# Sheet1.net
KiCad netlist of a schematic drawn in Altium Designer
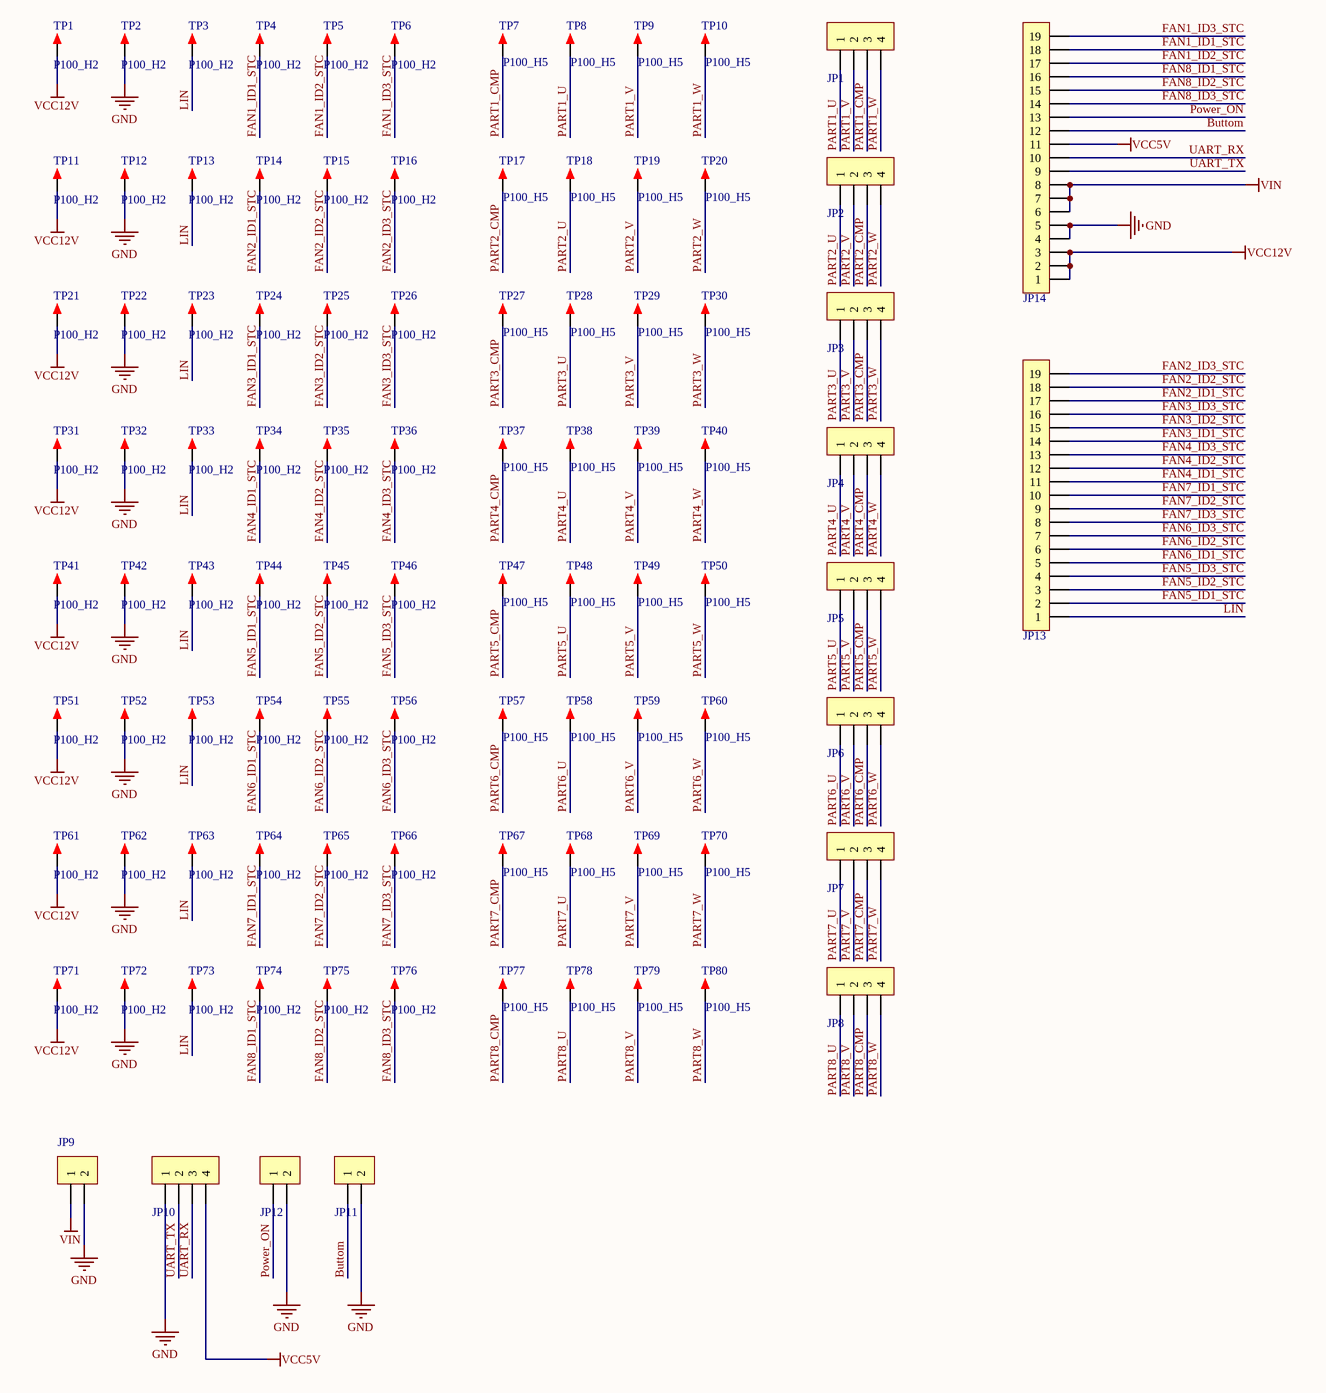
[diagram p0: Sheet1.SchDoc]

(export (version "E")
  (design (tool "Eeschema 10.0.6"))
  (components
    (comp (ref "JP1")
      (value "HDR-1X4")
      (footprint "XH2.54-WS-4P")
      (description "4P接插件")
      (fields (field (name "版权归属") "源创客"))
      (libsource (lib "Connector-PinHeader") (part "Header 4"))
    )
    (comp (ref "JP2")
      (value "HDR-1X4")
      (footprint "XH2.54-WS-4P")
      (description "4P接插件")
      (fields (field (name "版权归属") "源创客"))
      (libsource (lib "Connector-PinHeader") (part "Header 4"))
    )
    (comp (ref "JP3")
      (value "HDR-1X4")
      (footprint "XH2.54-WS-4P")
      (description "4P接插件")
      (fields (field (name "版权归属") "源创客"))
      (libsource (lib "Connector-PinHeader") (part "Header 4"))
    )
    (comp (ref "JP4")
      (value "HDR-1X4")
      (footprint "XH2.54-WS-4P")
      (description "4P接插件")
      (fields (field (name "版权归属") "源创客"))
      (libsource (lib "Connector-PinHeader") (part "Header 4"))
    )
    (comp (ref "JP5")
      (value "HDR-1X4")
      (footprint "XH2.54-WS-4P")
      (description "4P接插件")
      (fields (field (name "版权归属") "源创客"))
      (libsource (lib "Connector-PinHeader") (part "Header 4"))
    )
    (comp (ref "JP6")
      (value "HDR-1X4")
      (footprint "XH2.54-WS-4P")
      (description "4P接插件")
      (fields (field (name "版权归属") "源创客"))
      (libsource (lib "Connector-PinHeader") (part "Header 4"))
    )
    (comp (ref "JP7")
      (value "HDR-1X4")
      (footprint "XH2.54-WS-4P")
      (description "4P接插件")
      (fields (field (name "版权归属") "源创客"))
      (libsource (lib "Connector-PinHeader") (part "Header 4"))
    )
    (comp (ref "JP8")
      (value "HDR-1X4")
      (footprint "XH2.54-WS-4P")
      (description "4P接插件")
      (fields (field (name "版权归属") "源创客"))
      (libsource (lib "Connector-PinHeader") (part "Header 4"))
    )
    (comp (ref "JP9")
      (value "HDR-1X2")
      (footprint "DC-005P")
      (description "2P接插件")
      (fields (field (name "版权归属") "源创客"))
      (libsource (lib "Connector-PinHeader") (part "Header 2"))
    )
    (comp (ref "JP10")
      (value "HDR-1X4")
      (footprint "XH2.54-WS-4P")
      (description "4P接插件")
      (fields (field (name "版权归属") "源创客"))
      (libsource (lib "Connector-PinHeader") (part "Header 4"))
    )
    (comp (ref "JP11")
      (value "HDR-1X2")
      (footprint "XH2.54-WS-2P")
      (description "2P接插件")
      (fields (field (name "版权归属") "源创客"))
      (libsource (lib "Connector-PinHeader") (part "Header 2"))
    )
    (comp (ref "JP12")
      (value "HDR-1X2")
      (footprint "XH2.54-WS-2P")
      (description "2P接插件")
      (fields (field (name "版权归属") "源创客"))
      (libsource (lib "Connector-PinHeader") (part "Header 2"))
    )
    (comp (ref "JP13")
      (value "HDR-1X19")
      (footprint "贴片排针2.54mm_交错_19P")
      (description "19P接插件")
      (fields (field (name "版权归属") "源创客"))
      (libsource (lib "Connector-PinHeader") (part "Header 19"))
    )
    (comp (ref "JP14")
      (value "HDR-1X19")
      (footprint "贴片排针2.54mm_交错_19P")
      (description "19P接插件")
      (fields (field (name "版权归属") "源创客"))
      (libsource (lib "Connector-PinHeader") (part "Header 19"))
    )
    (comp (ref "TP1")
      (value "P100_H2")
      (footprint "P100_H2")
      (description "测试点")
      (fields (field (name "版权归属") "源创客"))
      (libsource (lib "Hole") (part "TEST"))
    )
    (comp (ref "TP2")
      (value "P100_H2")
      (footprint "P100_H2")
      (description "测试点")
      (fields (field (name "版权归属") "源创客"))
      (libsource (lib "Hole") (part "TEST"))
    )
    (comp (ref "TP3")
      (value "P100_H2")
      (footprint "P100_H2")
      (description "测试点")
      (fields (field (name "版权归属") "源创客"))
      (libsource (lib "Hole") (part "TEST"))
    )
    (comp (ref "TP4")
      (value "P100_H2")
      (footprint "P100_H2")
      (description "测试点")
      (fields (field (name "版权归属") "源创客"))
      (libsource (lib "Hole") (part "TEST"))
    )
    (comp (ref "TP5")
      (value "P100_H2")
      (footprint "P100_H2")
      (description "测试点")
      (fields (field (name "版权归属") "源创客"))
      (libsource (lib "Hole") (part "TEST"))
    )
    (comp (ref "TP6")
      (value "P100_H2")
      (footprint "P100_H2")
      (description "测试点")
      (fields (field (name "版权归属") "源创客"))
      (libsource (lib "Hole") (part "TEST"))
    )
    (comp (ref "TP7")
      (value "P100_H5")
      (footprint "P100_H5")
      (description "测试点")
      (fields (field (name "版权归属") "源创客"))
      (libsource (lib "Hole") (part "TEST"))
    )
    (comp (ref "TP8")
      (value "P100_H5")
      (footprint "P100_H5")
      (description "测试点")
      (fields (field (name "版权归属") "源创客"))
      (libsource (lib "Hole") (part "TEST"))
    )
    (comp (ref "TP9")
      (value "P100_H5")
      (footprint "P100_H5")
      (description "测试点")
      (fields (field (name "版权归属") "源创客"))
      (libsource (lib "Hole") (part "TEST"))
    )
    (comp (ref "TP10")
      (value "P100_H5")
      (footprint "P100_H5")
      (description "测试点")
      (fields (field (name "版权归属") "源创客"))
      (libsource (lib "Hole") (part "TEST"))
    )
    (comp (ref "TP11")
      (value "P100_H2")
      (footprint "P100_H2")
      (description "测试点")
      (fields (field (name "版权归属") "源创客"))
      (libsource (lib "Hole") (part "TEST"))
    )
    (comp (ref "TP12")
      (value "P100_H2")
      (footprint "P100_H2")
      (description "测试点")
      (fields (field (name "版权归属") "源创客"))
      (libsource (lib "Hole") (part "TEST"))
    )
    (comp (ref "TP13")
      (value "P100_H2")
      (footprint "P100_H2")
      (description "测试点")
      (fields (field (name "版权归属") "源创客"))
      (libsource (lib "Hole") (part "TEST"))
    )
    (comp (ref "TP14")
      (value "P100_H2")
      (footprint "P100_H2")
      (description "测试点")
      (fields (field (name "版权归属") "源创客"))
      (libsource (lib "Hole") (part "TEST"))
    )
    (comp (ref "TP15")
      (value "P100_H2")
      (footprint "P100_H2")
      (description "测试点")
      (fields (field (name "版权归属") "源创客"))
      (libsource (lib "Hole") (part "TEST"))
    )
    (comp (ref "TP16")
      (value "P100_H2")
      (footprint "P100_H2")
      (description "测试点")
      (fields (field (name "版权归属") "源创客"))
      (libsource (lib "Hole") (part "TEST"))
    )
    (comp (ref "TP17")
      (value "P100_H5")
      (footprint "P100_H5")
      (description "测试点")
      (fields (field (name "版权归属") "源创客"))
      (libsource (lib "Hole") (part "TEST"))
    )
    (comp (ref "TP18")
      (value "P100_H5")
      (footprint "P100_H5")
      (description "测试点")
      (fields (field (name "版权归属") "源创客"))
      (libsource (lib "Hole") (part "TEST"))
    )
    (comp (ref "TP19")
      (value "P100_H5")
      (footprint "P100_H5")
      (description "测试点")
      (fields (field (name "版权归属") "源创客"))
      (libsource (lib "Hole") (part "TEST"))
    )
    (comp (ref "TP20")
      (value "P100_H5")
      (footprint "P100_H5")
      (description "测试点")
      (fields (field (name "版权归属") "源创客"))
      (libsource (lib "Hole") (part "TEST"))
    )
    (comp (ref "TP21")
      (value "P100_H2")
      (footprint "P100_H2")
      (description "测试点")
      (fields (field (name "版权归属") "源创客"))
      (libsource (lib "Hole") (part "TEST"))
    )
    (comp (ref "TP22")
      (value "P100_H2")
      (footprint "P100_H2")
      (description "测试点")
      (fields (field (name "版权归属") "源创客"))
      (libsource (lib "Hole") (part "TEST"))
    )
    (comp (ref "TP23")
      (value "P100_H2")
      (footprint "P100_H2")
      (description "测试点")
      (fields (field (name "版权归属") "源创客"))
      (libsource (lib "Hole") (part "TEST"))
    )
    (comp (ref "TP24")
      (value "P100_H2")
      (footprint "P100_H2")
      (description "测试点")
      (fields (field (name "版权归属") "源创客"))
      (libsource (lib "Hole") (part "TEST"))
    )
    (comp (ref "TP25")
      (value "P100_H2")
      (footprint "P100_H2")
      (description "测试点")
      (fields (field (name "版权归属") "源创客"))
      (libsource (lib "Hole") (part "TEST"))
    )
    (comp (ref "TP26")
      (value "P100_H2")
      (footprint "P100_H2")
      (description "测试点")
      (fields (field (name "版权归属") "源创客"))
      (libsource (lib "Hole") (part "TEST"))
    )
    (comp (ref "TP27")
      (value "P100_H5")
      (footprint "P100_H5")
      (description "测试点")
      (fields (field (name "版权归属") "源创客"))
      (libsource (lib "Hole") (part "TEST"))
    )
    (comp (ref "TP28")
      (value "P100_H5")
      (footprint "P100_H5")
      (description "测试点")
      (fields (field (name "版权归属") "源创客"))
      (libsource (lib "Hole") (part "TEST"))
    )
    (comp (ref "TP29")
      (value "P100_H5")
      (footprint "P100_H5")
      (description "测试点")
      (fields (field (name "版权归属") "源创客"))
      (libsource (lib "Hole") (part "TEST"))
    )
    (comp (ref "TP30")
      (value "P100_H5")
      (footprint "P100_H5")
      (description "测试点")
      (fields (field (name "版权归属") "源创客"))
      (libsource (lib "Hole") (part "TEST"))
    )
    (comp (ref "TP31")
      (value "P100_H2")
      (footprint "P100_H2")
      (description "测试点")
      (fields (field (name "版权归属") "源创客"))
      (libsource (lib "Hole") (part "TEST"))
    )
    (comp (ref "TP32")
      (value "P100_H2")
      (footprint "P100_H2")
      (description "测试点")
      (fields (field (name "版权归属") "源创客"))
      (libsource (lib "Hole") (part "TEST"))
    )
    (comp (ref "TP33")
      (value "P100_H2")
      (footprint "P100_H2")
      (description "测试点")
      (fields (field (name "版权归属") "源创客"))
      (libsource (lib "Hole") (part "TEST"))
    )
    (comp (ref "TP34")
      (value "P100_H2")
      (footprint "P100_H2")
      (description "测试点")
      (fields (field (name "版权归属") "源创客"))
      (libsource (lib "Hole") (part "TEST"))
    )
    (comp (ref "TP35")
      (value "P100_H2")
      (footprint "P100_H2")
      (description "测试点")
      (fields (field (name "版权归属") "源创客"))
      (libsource (lib "Hole") (part "TEST"))
    )
    (comp (ref "TP36")
      (value "P100_H2")
      (footprint "P100_H2")
      (description "测试点")
      (fields (field (name "版权归属") "源创客"))
      (libsource (lib "Hole") (part "TEST"))
    )
    (comp (ref "TP37")
      (value "P100_H5")
      (footprint "P100_H5")
      (description "测试点")
      (fields (field (name "版权归属") "源创客"))
      (libsource (lib "Hole") (part "TEST"))
    )
    (comp (ref "TP38")
      (value "P100_H5")
      (footprint "P100_H5")
      (description "测试点")
      (fields (field (name "版权归属") "源创客"))
      (libsource (lib "Hole") (part "TEST"))
    )
    (comp (ref "TP39")
      (value "P100_H5")
      (footprint "P100_H5")
      (description "测试点")
      (fields (field (name "版权归属") "源创客"))
      (libsource (lib "Hole") (part "TEST"))
    )
    (comp (ref "TP40")
      (value "P100_H5")
      (footprint "P100_H5")
      (description "测试点")
      (fields (field (name "版权归属") "源创客"))
      (libsource (lib "Hole") (part "TEST"))
    )
    (comp (ref "TP41")
      (value "P100_H2")
      (footprint "P100_H2")
      (description "测试点")
      (fields (field (name "版权归属") "源创客"))
      (libsource (lib "Hole") (part "TEST"))
    )
    (comp (ref "TP42")
      (value "P100_H2")
      (footprint "P100_H2")
      (description "测试点")
      (fields (field (name "版权归属") "源创客"))
      (libsource (lib "Hole") (part "TEST"))
    )
    (comp (ref "TP43")
      (value "P100_H2")
      (footprint "P100_H2")
      (description "测试点")
      (fields (field (name "版权归属") "源创客"))
      (libsource (lib "Hole") (part "TEST"))
    )
    (comp (ref "TP44")
      (value "P100_H2")
      (footprint "P100_H2")
      (description "测试点")
      (fields (field (name "版权归属") "源创客"))
      (libsource (lib "Hole") (part "TEST"))
    )
    (comp (ref "TP45")
      (value "P100_H2")
      (footprint "P100_H2")
      (description "测试点")
      (fields (field (name "版权归属") "源创客"))
      (libsource (lib "Hole") (part "TEST"))
    )
    (comp (ref "TP46")
      (value "P100_H2")
      (footprint "P100_H2")
      (description "测试点")
      (fields (field (name "版权归属") "源创客"))
      (libsource (lib "Hole") (part "TEST"))
    )
    (comp (ref "TP47")
      (value "P100_H5")
      (footprint "P100_H5")
      (description "测试点")
      (fields (field (name "版权归属") "源创客"))
      (libsource (lib "Hole") (part "TEST"))
    )
    (comp (ref "TP48")
      (value "P100_H5")
      (footprint "P100_H5")
      (description "测试点")
      (fields (field (name "版权归属") "源创客"))
      (libsource (lib "Hole") (part "TEST"))
    )
    (comp (ref "TP49")
      (value "P100_H5")
      (footprint "P100_H5")
      (description "测试点")
      (fields (field (name "版权归属") "源创客"))
      (libsource (lib "Hole") (part "TEST"))
    )
    (comp (ref "TP50")
      (value "P100_H5")
      (footprint "P100_H5")
      (description "测试点")
      (fields (field (name "版权归属") "源创客"))
      (libsource (lib "Hole") (part "TEST"))
    )
    (comp (ref "TP51")
      (value "P100_H2")
      (footprint "P100_H2")
      (description "测试点")
      (fields (field (name "版权归属") "源创客"))
      (libsource (lib "Hole") (part "TEST"))
    )
    (comp (ref "TP52")
      (value "P100_H2")
      (footprint "P100_H2")
      (description "测试点")
      (fields (field (name "版权归属") "源创客"))
      (libsource (lib "Hole") (part "TEST"))
    )
    (comp (ref "TP53")
      (value "P100_H2")
      (footprint "P100_H2")
      (description "测试点")
      (fields (field (name "版权归属") "源创客"))
      (libsource (lib "Hole") (part "TEST"))
    )
    (comp (ref "TP54")
      (value "P100_H2")
      (footprint "P100_H2")
      (description "测试点")
      (fields (field (name "版权归属") "源创客"))
      (libsource (lib "Hole") (part "TEST"))
    )
    (comp (ref "TP55")
      (value "P100_H2")
      (footprint "P100_H2")
      (description "测试点")
      (fields (field (name "版权归属") "源创客"))
      (libsource (lib "Hole") (part "TEST"))
    )
    (comp (ref "TP56")
      (value "P100_H2")
      (footprint "P100_H2")
      (description "测试点")
      (fields (field (name "版权归属") "源创客"))
      (libsource (lib "Hole") (part "TEST"))
    )
    (comp (ref "TP57")
      (value "P100_H5")
      (footprint "P100_H5")
      (description "测试点")
      (fields (field (name "版权归属") "源创客"))
      (libsource (lib "Hole") (part "TEST"))
    )
    (comp (ref "TP58")
      (value "P100_H5")
      (footprint "P100_H5")
      (description "测试点")
      (fields (field (name "版权归属") "源创客"))
      (libsource (lib "Hole") (part "TEST"))
    )
    (comp (ref "TP59")
      (value "P100_H5")
      (footprint "P100_H5")
      (description "测试点")
      (fields (field (name "版权归属") "源创客"))
      (libsource (lib "Hole") (part "TEST"))
    )
    (comp (ref "TP60")
      (value "P100_H5")
      (footprint "P100_H5")
      (description "测试点")
      (fields (field (name "版权归属") "源创客"))
      (libsource (lib "Hole") (part "TEST"))
    )
    (comp (ref "TP61")
      (value "P100_H2")
      (footprint "P100_H2")
      (description "测试点")
      (fields (field (name "版权归属") "源创客"))
      (libsource (lib "Hole") (part "TEST"))
    )
    (comp (ref "TP62")
      (value "P100_H2")
      (footprint "P100_H2")
      (description "测试点")
      (fields (field (name "版权归属") "源创客"))
      (libsource (lib "Hole") (part "TEST"))
    )
    (comp (ref "TP63")
      (value "P100_H2")
      (footprint "P100_H2")
      (description "测试点")
      (fields (field (name "版权归属") "源创客"))
      (libsource (lib "Hole") (part "TEST"))
    )
    (comp (ref "TP64")
      (value "P100_H2")
      (footprint "P100_H2")
      (description "测试点")
      (fields (field (name "版权归属") "源创客"))
      (libsource (lib "Hole") (part "TEST"))
    )
    (comp (ref "TP65")
      (value "P100_H2")
      (footprint "P100_H2")
      (description "测试点")
      (fields (field (name "版权归属") "源创客"))
      (libsource (lib "Hole") (part "TEST"))
    )
    (comp (ref "TP66")
      (value "P100_H2")
      (footprint "P100_H2")
      (description "测试点")
      (fields (field (name "版权归属") "源创客"))
      (libsource (lib "Hole") (part "TEST"))
    )
    (comp (ref "TP67")
      (value "P100_H5")
      (footprint "P100_H5")
      (description "测试点")
      (fields (field (name "版权归属") "源创客"))
      (libsource (lib "Hole") (part "TEST"))
    )
    (comp (ref "TP68")
      (value "P100_H5")
      (footprint "P100_H5")
      (description "测试点")
      (fields (field (name "版权归属") "源创客"))
      (libsource (lib "Hole") (part "TEST"))
    )
    (comp (ref "TP69")
      (value "P100_H5")
      (footprint "P100_H5")
      (description "测试点")
      (fields (field (name "版权归属") "源创客"))
      (libsource (lib "Hole") (part "TEST"))
    )
    (comp (ref "TP70")
      (value "P100_H5")
      (footprint "P100_H5")
      (description "测试点")
      (fields (field (name "版权归属") "源创客"))
      (libsource (lib "Hole") (part "TEST"))
    )
    (comp (ref "TP71")
      (value "P100_H2")
      (footprint "P100_H2")
      (description "测试点")
      (fields (field (name "版权归属") "源创客"))
      (libsource (lib "Hole") (part "TEST"))
    )
    (comp (ref "TP72")
      (value "P100_H2")
      (footprint "P100_H2")
      (description "测试点")
      (fields (field (name "版权归属") "源创客"))
      (libsource (lib "Hole") (part "TEST"))
    )
    (comp (ref "TP73")
      (value "P100_H2")
      (footprint "P100_H2")
      (description "测试点")
      (fields (field (name "版权归属") "源创客"))
      (libsource (lib "Hole") (part "TEST"))
    )
    (comp (ref "TP74")
      (value "P100_H2")
      (footprint "P100_H2")
      (description "测试点")
      (fields (field (name "版权归属") "源创客"))
      (libsource (lib "Hole") (part "TEST"))
    )
    (comp (ref "TP75")
      (value "P100_H2")
      (footprint "P100_H2")
      (description "测试点")
      (fields (field (name "版权归属") "源创客"))
      (libsource (lib "Hole") (part "TEST"))
    )
    (comp (ref "TP76")
      (value "P100_H2")
      (footprint "P100_H2")
      (description "测试点")
      (fields (field (name "版权归属") "源创客"))
      (libsource (lib "Hole") (part "TEST"))
    )
    (comp (ref "TP77")
      (value "P100_H5")
      (footprint "P100_H5")
      (description "测试点")
      (fields (field (name "版权归属") "源创客"))
      (libsource (lib "Hole") (part "TEST"))
    )
    (comp (ref "TP78")
      (value "P100_H5")
      (footprint "P100_H5")
      (description "测试点")
      (fields (field (name "版权归属") "源创客"))
      (libsource (lib "Hole") (part "TEST"))
    )
    (comp (ref "TP79")
      (value "P100_H5")
      (footprint "P100_H5")
      (description "测试点")
      (fields (field (name "版权归属") "源创客"))
      (libsource (lib "Hole") (part "TEST"))
    )
    (comp (ref "TP80")
      (value "P100_H5")
      (footprint "P100_H5")
      (description "测试点")
      (fields (field (name "版权归属") "源创客"))
      (libsource (lib "Hole") (part "TEST"))
    )
  )
  (nets
    (net (code "1") (name "/Buttom") (class "Default")
      (node (ref "JP11") (pin "1") (pinfunction "1_1") (pintype "passive"))
      (node (ref "JP14") (pin "12") (pinfunction "12_12") (pintype "passive"))
    )
    (net (code "2") (name "/FAN1_ID1_STC") (class "Default")
      (node (ref "JP14") (pin "18") (pinfunction "18_18") (pintype "passive"))
      (node (ref "TP4") (pin "1") (pinfunction "1_1") (pintype "passive"))
    )
    (net (code "3") (name "/FAN1_ID2_STC") (class "Default")
      (node (ref "JP14") (pin "17") (pinfunction "17_17") (pintype "passive"))
      (node (ref "TP5") (pin "1") (pinfunction "1_1") (pintype "passive"))
    )
    (net (code "4") (name "/FAN1_ID3_STC") (class "Default")
      (node (ref "JP14") (pin "19") (pinfunction "19_19") (pintype "passive"))
      (node (ref "TP6") (pin "1") (pinfunction "1_1") (pintype "passive"))
    )
    (net (code "5") (name "/FAN2_ID1_STC") (class "Default")
      (node (ref "JP13") (pin "17") (pinfunction "17_17") (pintype "passive"))
      (node (ref "TP14") (pin "1") (pinfunction "1_1") (pintype "passive"))
    )
    (net (code "6") (name "/FAN2_ID2_STC") (class "Default")
      (node (ref "JP13") (pin "18") (pinfunction "18_18") (pintype "passive"))
      (node (ref "TP15") (pin "1") (pinfunction "1_1") (pintype "passive"))
    )
    (net (code "7") (name "/FAN2_ID3_STC") (class "Default")
      (node (ref "JP13") (pin "19") (pinfunction "19_19") (pintype "passive"))
      (node (ref "TP16") (pin "1") (pinfunction "1_1") (pintype "passive"))
    )
    (net (code "8") (name "/FAN3_ID1_STC") (class "Default")
      (node (ref "JP13") (pin "14") (pinfunction "14_14") (pintype "passive"))
      (node (ref "TP24") (pin "1") (pinfunction "1_1") (pintype "passive"))
    )
    (net (code "9") (name "/FAN3_ID2_STC") (class "Default")
      (node (ref "JP13") (pin "15") (pinfunction "15_15") (pintype "passive"))
      (node (ref "TP25") (pin "1") (pinfunction "1_1") (pintype "passive"))
    )
    (net (code "10") (name "/FAN3_ID3_STC") (class "Default")
      (node (ref "JP13") (pin "16") (pinfunction "16_16") (pintype "passive"))
      (node (ref "TP26") (pin "1") (pinfunction "1_1") (pintype "passive"))
    )
    (net (code "11") (name "/FAN4_ID1_STC") (class "Default")
      (node (ref "JP13") (pin "11") (pinfunction "11_11") (pintype "passive"))
      (node (ref "TP34") (pin "1") (pinfunction "1_1") (pintype "passive"))
    )
    (net (code "12") (name "/FAN4_ID2_STC") (class "Default")
      (node (ref "JP13") (pin "12") (pinfunction "12_12") (pintype "passive"))
      (node (ref "TP35") (pin "1") (pinfunction "1_1") (pintype "passive"))
    )
    (net (code "13") (name "/FAN4_ID3_STC") (class "Default")
      (node (ref "JP13") (pin "13") (pinfunction "13_13") (pintype "passive"))
      (node (ref "TP36") (pin "1") (pinfunction "1_1") (pintype "passive"))
    )
    (net (code "14") (name "/FAN5_ID1_STC") (class "Default")
      (node (ref "JP13") (pin "2") (pinfunction "2_2") (pintype "passive"))
      (node (ref "TP44") (pin "1") (pinfunction "1_1") (pintype "passive"))
    )
    (net (code "15") (name "/FAN5_ID2_STC") (class "Default")
      (node (ref "JP13") (pin "3") (pinfunction "3_3") (pintype "passive"))
      (node (ref "TP45") (pin "1") (pinfunction "1_1") (pintype "passive"))
    )
    (net (code "16") (name "/FAN5_ID3_STC") (class "Default")
      (node (ref "JP13") (pin "4") (pinfunction "4_4") (pintype "passive"))
      (node (ref "TP46") (pin "1") (pinfunction "1_1") (pintype "passive"))
    )
    (net (code "17") (name "/FAN6_ID1_STC") (class "Default")
      (node (ref "JP13") (pin "5") (pinfunction "5_5") (pintype "passive"))
      (node (ref "TP54") (pin "1") (pinfunction "1_1") (pintype "passive"))
    )
    (net (code "18") (name "/FAN6_ID2_STC") (class "Default")
      (node (ref "JP13") (pin "6") (pinfunction "6_6") (pintype "passive"))
      (node (ref "TP55") (pin "1") (pinfunction "1_1") (pintype "passive"))
    )
    (net (code "19") (name "/FAN6_ID3_STC") (class "Default")
      (node (ref "JP13") (pin "7") (pinfunction "7_7") (pintype "passive"))
      (node (ref "TP56") (pin "1") (pinfunction "1_1") (pintype "passive"))
    )
    (net (code "20") (name "/FAN7_ID1_STC") (class "Default")
      (node (ref "JP13") (pin "10") (pinfunction "10_10") (pintype "passive"))
      (node (ref "TP64") (pin "1") (pinfunction "1_1") (pintype "passive"))
    )
    (net (code "21") (name "/FAN7_ID2_STC") (class "Default")
      (node (ref "JP13") (pin "9") (pinfunction "9_9") (pintype "passive"))
      (node (ref "TP65") (pin "1") (pinfunction "1_1") (pintype "passive"))
    )
    (net (code "22") (name "/FAN7_ID3_STC") (class "Default")
      (node (ref "JP13") (pin "8") (pinfunction "8_8") (pintype "passive"))
      (node (ref "TP66") (pin "1") (pinfunction "1_1") (pintype "passive"))
    )
    (net (code "23") (name "/FAN8_ID1_STC") (class "Default")
      (node (ref "JP14") (pin "16") (pinfunction "16_16") (pintype "passive"))
      (node (ref "TP74") (pin "1") (pinfunction "1_1") (pintype "passive"))
    )
    (net (code "24") (name "/FAN8_ID2_STC") (class "Default")
      (node (ref "JP14") (pin "15") (pinfunction "15_15") (pintype "passive"))
      (node (ref "TP75") (pin "1") (pinfunction "1_1") (pintype "passive"))
    )
    (net (code "25") (name "/FAN8_ID3_STC") (class "Default")
      (node (ref "JP14") (pin "14") (pinfunction "14_14") (pintype "passive"))
      (node (ref "TP76") (pin "1") (pinfunction "1_1") (pintype "passive"))
    )
    (net (code "26") (name "/LIN") (class "Default")
      (node (ref "JP13") (pin "1") (pinfunction "1_1") (pintype "passive"))
      (node (ref "TP13") (pin "1") (pinfunction "1_1") (pintype "passive"))
      (node (ref "TP23") (pin "1") (pinfunction "1_1") (pintype "passive"))
      (node (ref "TP3") (pin "1") (pinfunction "1_1") (pintype "passive"))
      (node (ref "TP33") (pin "1") (pinfunction "1_1") (pintype "passive"))
      (node (ref "TP43") (pin "1") (pinfunction "1_1") (pintype "passive"))
      (node (ref "TP53") (pin "1") (pinfunction "1_1") (pintype "passive"))
      (node (ref "TP63") (pin "1") (pinfunction "1_1") (pintype "passive"))
      (node (ref "TP73") (pin "1") (pinfunction "1_1") (pintype "passive"))
    )
    (net (code "27") (name "/PART1_CMP") (class "Default")
      (node (ref "JP1") (pin "3") (pinfunction "3_3") (pintype "passive"))
      (node (ref "TP7") (pin "1") (pinfunction "1_1") (pintype "passive"))
    )
    (net (code "28") (name "/PART1_U") (class "Default")
      (node (ref "JP1") (pin "1") (pinfunction "1_1") (pintype "passive"))
      (node (ref "TP8") (pin "1") (pinfunction "1_1") (pintype "passive"))
    )
    (net (code "29") (name "/PART1_V") (class "Default")
      (node (ref "JP1") (pin "2") (pinfunction "2_2") (pintype "passive"))
      (node (ref "TP9") (pin "1") (pinfunction "1_1") (pintype "passive"))
    )
    (net (code "30") (name "/PART1_W") (class "Default")
      (node (ref "JP1") (pin "4") (pinfunction "4_4") (pintype "passive"))
      (node (ref "TP10") (pin "1") (pinfunction "1_1") (pintype "passive"))
    )
    (net (code "31") (name "/PART2_CMP") (class "Default")
      (node (ref "JP2") (pin "3") (pinfunction "3_3") (pintype "passive"))
      (node (ref "TP17") (pin "1") (pinfunction "1_1") (pintype "passive"))
    )
    (net (code "32") (name "/PART2_U") (class "Default")
      (node (ref "JP2") (pin "1") (pinfunction "1_1") (pintype "passive"))
      (node (ref "TP18") (pin "1") (pinfunction "1_1") (pintype "passive"))
    )
    (net (code "33") (name "/PART2_V") (class "Default")
      (node (ref "JP2") (pin "2") (pinfunction "2_2") (pintype "passive"))
      (node (ref "TP19") (pin "1") (pinfunction "1_1") (pintype "passive"))
    )
    (net (code "34") (name "/PART2_W") (class "Default")
      (node (ref "JP2") (pin "4") (pinfunction "4_4") (pintype "passive"))
      (node (ref "TP20") (pin "1") (pinfunction "1_1") (pintype "passive"))
    )
    (net (code "35") (name "/PART3_CMP") (class "Default")
      (node (ref "JP3") (pin "3") (pinfunction "3_3") (pintype "passive"))
      (node (ref "TP27") (pin "1") (pinfunction "1_1") (pintype "passive"))
    )
    (net (code "36") (name "/PART3_U") (class "Default")
      (node (ref "JP3") (pin "1") (pinfunction "1_1") (pintype "passive"))
      (node (ref "TP28") (pin "1") (pinfunction "1_1") (pintype "passive"))
    )
    (net (code "37") (name "/PART3_V") (class "Default")
      (node (ref "JP3") (pin "2") (pinfunction "2_2") (pintype "passive"))
      (node (ref "TP29") (pin "1") (pinfunction "1_1") (pintype "passive"))
    )
    (net (code "38") (name "/PART3_W") (class "Default")
      (node (ref "JP3") (pin "4") (pinfunction "4_4") (pintype "passive"))
      (node (ref "TP30") (pin "1") (pinfunction "1_1") (pintype "passive"))
    )
    (net (code "39") (name "/PART4_CMP") (class "Default")
      (node (ref "JP4") (pin "3") (pinfunction "3_3") (pintype "passive"))
      (node (ref "TP37") (pin "1") (pinfunction "1_1") (pintype "passive"))
    )
    (net (code "40") (name "/PART4_U") (class "Default")
      (node (ref "JP4") (pin "1") (pinfunction "1_1") (pintype "passive"))
      (node (ref "TP38") (pin "1") (pinfunction "1_1") (pintype "passive"))
    )
    (net (code "41") (name "/PART4_V") (class "Default")
      (node (ref "JP4") (pin "2") (pinfunction "2_2") (pintype "passive"))
      (node (ref "TP39") (pin "1") (pinfunction "1_1") (pintype "passive"))
    )
    (net (code "42") (name "/PART4_W") (class "Default")
      (node (ref "JP4") (pin "4") (pinfunction "4_4") (pintype "passive"))
      (node (ref "TP40") (pin "1") (pinfunction "1_1") (pintype "passive"))
    )
    (net (code "43") (name "/PART5_CMP") (class "Default")
      (node (ref "JP5") (pin "3") (pinfunction "3_3") (pintype "passive"))
      (node (ref "TP47") (pin "1") (pinfunction "1_1") (pintype "passive"))
    )
    (net (code "44") (name "/PART5_U") (class "Default")
      (node (ref "JP5") (pin "1") (pinfunction "1_1") (pintype "passive"))
      (node (ref "TP48") (pin "1") (pinfunction "1_1") (pintype "passive"))
    )
    (net (code "45") (name "/PART5_V") (class "Default")
      (node (ref "JP5") (pin "2") (pinfunction "2_2") (pintype "passive"))
      (node (ref "TP49") (pin "1") (pinfunction "1_1") (pintype "passive"))
    )
    (net (code "46") (name "/PART5_W") (class "Default")
      (node (ref "JP5") (pin "4") (pinfunction "4_4") (pintype "passive"))
      (node (ref "TP50") (pin "1") (pinfunction "1_1") (pintype "passive"))
    )
    (net (code "47") (name "/PART6_CMP") (class "Default")
      (node (ref "JP6") (pin "3") (pinfunction "3_3") (pintype "passive"))
      (node (ref "TP57") (pin "1") (pinfunction "1_1") (pintype "passive"))
    )
    (net (code "48") (name "/PART6_U") (class "Default")
      (node (ref "JP6") (pin "1") (pinfunction "1_1") (pintype "passive"))
      (node (ref "TP58") (pin "1") (pinfunction "1_1") (pintype "passive"))
    )
    (net (code "49") (name "/PART6_V") (class "Default")
      (node (ref "JP6") (pin "2") (pinfunction "2_2") (pintype "passive"))
      (node (ref "TP59") (pin "1") (pinfunction "1_1") (pintype "passive"))
    )
    (net (code "50") (name "/PART6_W") (class "Default")
      (node (ref "JP6") (pin "4") (pinfunction "4_4") (pintype "passive"))
      (node (ref "TP60") (pin "1") (pinfunction "1_1") (pintype "passive"))
    )
    (net (code "51") (name "/PART7_CMP") (class "Default")
      (node (ref "JP7") (pin "3") (pinfunction "3_3") (pintype "passive"))
      (node (ref "TP67") (pin "1") (pinfunction "1_1") (pintype "passive"))
    )
    (net (code "52") (name "/PART7_U") (class "Default")
      (node (ref "JP7") (pin "1") (pinfunction "1_1") (pintype "passive"))
      (node (ref "TP68") (pin "1") (pinfunction "1_1") (pintype "passive"))
    )
    (net (code "53") (name "/PART7_V") (class "Default")
      (node (ref "JP7") (pin "2") (pinfunction "2_2") (pintype "passive"))
      (node (ref "TP69") (pin "1") (pinfunction "1_1") (pintype "passive"))
    )
    (net (code "54") (name "/PART7_W") (class "Default")
      (node (ref "JP7") (pin "4") (pinfunction "4_4") (pintype "passive"))
      (node (ref "TP70") (pin "1") (pinfunction "1_1") (pintype "passive"))
    )
    (net (code "55") (name "/PART8_CMP") (class "Default")
      (node (ref "JP8") (pin "3") (pinfunction "3_3") (pintype "passive"))
      (node (ref "TP77") (pin "1") (pinfunction "1_1") (pintype "passive"))
    )
    (net (code "56") (name "/PART8_U") (class "Default")
      (node (ref "JP8") (pin "1") (pinfunction "1_1") (pintype "passive"))
      (node (ref "TP78") (pin "1") (pinfunction "1_1") (pintype "passive"))
    )
    (net (code "57") (name "/PART8_V") (class "Default")
      (node (ref "JP8") (pin "2") (pinfunction "2_2") (pintype "passive"))
      (node (ref "TP79") (pin "1") (pinfunction "1_1") (pintype "passive"))
    )
    (net (code "58") (name "/PART8_W") (class "Default")
      (node (ref "JP8") (pin "4") (pinfunction "4_4") (pintype "passive"))
      (node (ref "TP80") (pin "1") (pinfunction "1_1") (pintype "passive"))
    )
    (net (code "59") (name "/Power_ON") (class "Default")
      (node (ref "JP12") (pin "1") (pinfunction "1_1") (pintype "passive"))
      (node (ref "JP14") (pin "13") (pinfunction "13_13") (pintype "passive"))
    )
    (net (code "60") (name "/UART_RX") (class "Default")
      (node (ref "JP10") (pin "3") (pinfunction "3_3") (pintype "passive"))
      (node (ref "JP14") (pin "10") (pinfunction "10_10") (pintype "passive"))
    )
    (net (code "61") (name "/UART_TX") (class "Default")
      (node (ref "JP10") (pin "2") (pinfunction "2_2") (pintype "passive"))
      (node (ref "JP14") (pin "9") (pinfunction "9_9") (pintype "passive"))
    )
    (net (code "62") (name "GND") (class "Default")
      (node (ref "JP10") (pin "1") (pinfunction "1_1") (pintype "passive"))
      (node (ref "JP11") (pin "2") (pinfunction "2_2") (pintype "passive"))
      (node (ref "JP12") (pin "2") (pinfunction "2_2") (pintype "passive"))
      (node (ref "JP14") (pin "4") (pinfunction "4_4") (pintype "passive"))
      (node (ref "JP14") (pin "5") (pinfunction "5_5") (pintype "passive"))
      (node (ref "JP9") (pin "2") (pinfunction "2_2") (pintype "passive"))
      (node (ref "TP12") (pin "1") (pinfunction "1_1") (pintype "passive"))
      (node (ref "TP2") (pin "1") (pinfunction "1_1") (pintype "passive"))
      (node (ref "TP22") (pin "1") (pinfunction "1_1") (pintype "passive"))
      (node (ref "TP32") (pin "1") (pinfunction "1_1") (pintype "passive"))
      (node (ref "TP42") (pin "1") (pinfunction "1_1") (pintype "passive"))
      (node (ref "TP52") (pin "1") (pinfunction "1_1") (pintype "passive"))
      (node (ref "TP62") (pin "1") (pinfunction "1_1") (pintype "passive"))
      (node (ref "TP72") (pin "1") (pinfunction "1_1") (pintype "passive"))
    )
    (net (code "63") (name "VCC5V") (class "Default")
      (node (ref "JP10") (pin "4") (pinfunction "4_4") (pintype "passive"))
      (node (ref "JP14") (pin "11") (pinfunction "11_11") (pintype "passive"))
    )
    (net (code "64") (name "VCC12V") (class "Default")
      (node (ref "JP14") (pin "1") (pinfunction "1_1") (pintype "passive"))
      (node (ref "JP14") (pin "2") (pinfunction "2_2") (pintype "passive"))
      (node (ref "JP14") (pin "3") (pinfunction "3_3") (pintype "passive"))
      (node (ref "TP1") (pin "1") (pinfunction "1_1") (pintype "passive"))
      (node (ref "TP11") (pin "1") (pinfunction "1_1") (pintype "passive"))
      (node (ref "TP21") (pin "1") (pinfunction "1_1") (pintype "passive"))
      (node (ref "TP31") (pin "1") (pinfunction "1_1") (pintype "passive"))
      (node (ref "TP41") (pin "1") (pinfunction "1_1") (pintype "passive"))
      (node (ref "TP51") (pin "1") (pinfunction "1_1") (pintype "passive"))
      (node (ref "TP61") (pin "1") (pinfunction "1_1") (pintype "passive"))
      (node (ref "TP71") (pin "1") (pinfunction "1_1") (pintype "passive"))
    )
    (net (code "65") (name "VIN") (class "Default")
      (node (ref "JP14") (pin "6") (pinfunction "6_6") (pintype "passive"))
      (node (ref "JP14") (pin "7") (pinfunction "7_7") (pintype "passive"))
      (node (ref "JP14") (pin "8") (pinfunction "8_8") (pintype "passive"))
      (node (ref "JP9") (pin "1") (pinfunction "1_1") (pintype "passive"))
    )
  )
)
